# STRAIN.net
KiCad netlist of a schematic drawn in Altium Designer
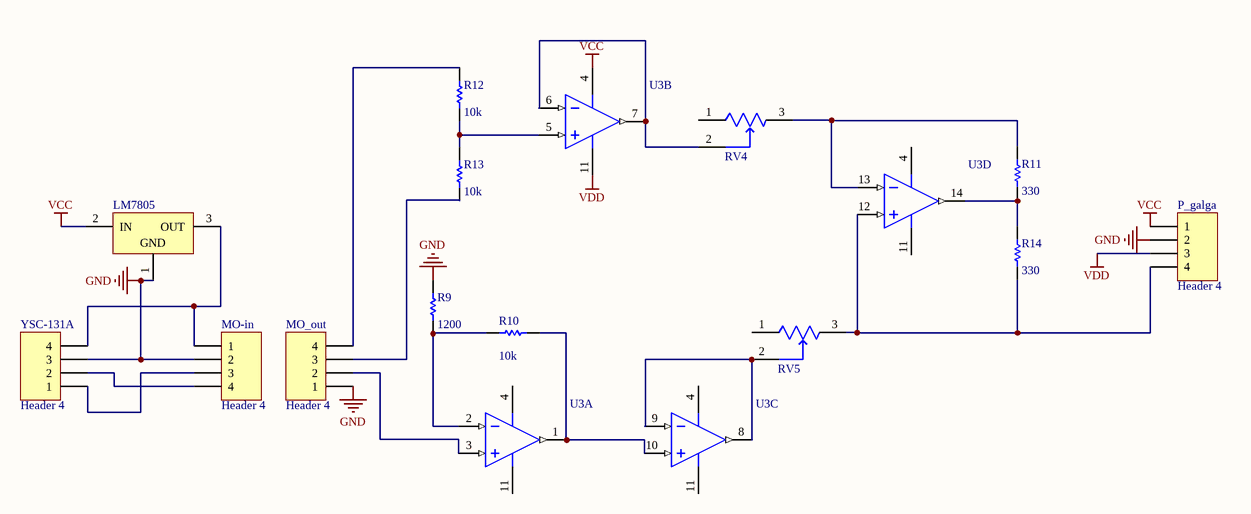
[diagram p0: STRAIN.SchDoc]

(export (version "E")
  (design (tool "Eeschema 10.0.6"))
  (components
    (comp (ref "LM7805")
      (value "LM7905CT/NOPB")
      (footprint "NDE0003A")
      (description "3-Terminal Negative Regulator, 3-pin TO-220, Pb-Free")
      (fields (field (name "MANUFACTURER") "Texas Instruments"))
      (libsource (lib "Altium Content Vault") (part "PM-REG-LM7905-SIL3"))
    )
    (comp (ref "MO-in")
      (value "Header 4")
      (footprint "HDR1X4")
      (description "Header, 4-Pin")
      (fields (field (name "PUBLISHER") "Altium Limited"))
      (libsource (lib "Miscellaneous Connectors") (part "Header 4"))
    )
    (comp (ref "MO_out")
      (value "Header 4")
      (footprint "HDR1X4")
      (description "Header, 4-Pin")
      (fields (field (name "PUBLISHER") "Altium Limited"))
      (libsource (lib "") (part "Header 4_1"))
    )
    (comp (ref "P_galga")
      (value "Header 4")
      (footprint "HDR1X4")
      (description "Header, 4-Pin")
      (fields (field (name "PUBLISHER") "Altium Limited"))
      (libsource (lib "Miscellaneous Connectors") (part "Header 4"))
    )
    (comp (ref "R9")
      (value "1200")
      (footprint "AXIAL-0.3")
      (description "Resistor")
      (fields (field (name "Comment") "Res1") (field (name "PUBLISHER") "Altium Limited"))
      (libsource (lib "Miscellaneous Devices") (part "Res1"))
    )
    (comp (ref "R10")
      (value "10k")
      (footprint "AXIAL-0.3")
      (description "Resistor")
      (fields (field (name "Comment") "Res1") (field (name "PUBLISHER") "Altium Limited"))
      (libsource (lib "Miscellaneous Devices") (part "Res1"))
    )
    (comp (ref "R11")
      (value "330")
      (footprint "AXIAL-0.3")
      (description "Resistor")
      (fields (field (name "Comment") "Res1") (field (name "PUBLISHER") "Altium Limited"))
      (libsource (lib "Miscellaneous Devices") (part "Res1"))
    )
    (comp (ref "R12")
      (value "10k")
      (footprint "AXIAL-0.3")
      (description "Resistor")
      (fields (field (name "Comment") "Res1") (field (name "PUBLISHER") "Altium Limited"))
      (libsource (lib "Miscellaneous Devices") (part "Res1"))
    )
    (comp (ref "R13")
      (value "10k")
      (footprint "AXIAL-0.3")
      (description "Resistor")
      (fields (field (name "Comment") "Res1") (field (name "PUBLISHER") "Altium Limited"))
      (libsource (lib "Miscellaneous Devices") (part "Res1"))
    )
    (comp (ref "R14")
      (value "330")
      (footprint "AXIAL-0.3")
      (description "Resistor")
      (fields (field (name "Comment") "Res1") (field (name "PUBLISHER") "Altium Limited"))
      (libsource (lib "Miscellaneous Devices") (part "Res1"))
    )
    (comp (ref "RV4")
      (value "3296W-1-504LF")
      (footprint "FP-3296W-MFG")
      (description "TRIMMER 500K OHM 0.5W PC PIN TOP")
      (fields
        (field (name "MANUFACTURER") "Bourns")
        (field (name "OCTOPART") "https://octopart.com/3296w-1-504lf-bourns-143884")
      )
      (libsource (lib "Altium Content Vault") (part "8d460c8a6f7ec10b1759d1b9c49aa93"))
    )
    (comp (ref "RV5")
      (value "3296W-1-504LF")
      (footprint "FP-3296W-MFG")
      (description "TRIMMER 500K OHM 0.5W PC PIN TOP")
      (fields
        (field (name "MANUFACTURER") "Bourns")
        (field (name "OCTOPART") "https://octopart.com/3296w-1-504lf-bourns-143884")
      )
      (libsource (lib "Altium Content Vault") (part "8d460c8a6f7ec10b1759d1b9c49aa93"))
    )
    (comp (ref "U3")
      (value "LF347N")
      (footprint "N0014A")
      (description "Wide Bandwidth Quad JFET Input Operational Amplifier, 14-pin MDIP")
      (fields (field (name "MANUFACTURER") "Texas Instruments"))
      (libsource (lib "Altium Content Vault") (part "AMP-OPA-LF147-14"))
    )
    (comp (ref "YSC-131A")
      (value "Header 4")
      (footprint "HDR1X4")
      (description "Header, 4-Pin")
      (fields (field (name "PUBLISHER") "Altium Limited"))
      (libsource (lib "") (part "Header 4_1"))
    )
  )
  (nets
    (net (code "1") (name "GND") (class "Default")
      (node (ref "LM7805") (pin "1") (pinfunction "GND_1") (pintype "power_in"))
      (node (ref "MO-in") (pin "2") (pinfunction "2_2") (pintype "passive"))
      (node (ref "MO_out") (pin "1") (pinfunction "1_1") (pintype "passive"))
      (node (ref "P_galga") (pin "2") (pinfunction "2_2") (pintype "passive"))
      (node (ref "R9") (pin "2") (pinfunction "2_2") (pintype "passive"))
      (node (ref "YSC-131A") (pin "3") (pinfunction "3_3") (pintype "passive"))
    )
    (net (code "2") (name "Net-(LM7805-OUT)") (class "Default")
      (node (ref "LM7805") (pin "3") (pinfunction "OUT_3") (pintype "power_in"))
      (node (ref "MO-in") (pin "1") (pinfunction "1_1") (pintype "passive"))
      (node (ref "YSC-131A") (pin "4") (pinfunction "4_4") (pintype "passive"))
    )
    (net (code "3") (name "Net-(MO-in-Pad3)") (class "Default")
      (node (ref "MO-in") (pin "3") (pinfunction "3_3") (pintype "passive"))
      (node (ref "YSC-131A") (pin "1") (pinfunction "1_1") (pintype "passive"))
    )
    (net (code "4") (name "Net-(MO-in-Pad4)") (class "Default")
      (node (ref "MO-in") (pin "4") (pinfunction "4_4") (pintype "passive"))
      (node (ref "YSC-131A") (pin "2") (pinfunction "2_2") (pintype "passive"))
    )
    (net (code "5") (name "Net-(MO_out-Pad3)") (class "Default")
      (node (ref "MO_out") (pin "3") (pinfunction "3_3") (pintype "passive"))
      (node (ref "R13") (pin "1") (pinfunction "1_1") (pintype "passive"))
    )
    (net (code "6") (name "Net-(MO_out-Pad4)") (class "Default")
      (node (ref "MO_out") (pin "4") (pinfunction "4_4") (pintype "passive"))
      (node (ref "R12") (pin "2") (pinfunction "2_2") (pintype "passive"))
    )
    (net (code "7") (name "Net-(RV4-CW)") (class "Default")
      (node (ref "R11") (pin "2") (pinfunction "2_2") (pintype "passive"))
      (node (ref "RV4") (pin "3") (pinfunction "CW_3") (pintype "passive"))
      (node (ref "U3") (pin "13") (pinfunction "IN4-_13") (pintype "input"))
    )
    (net (code "8") (name "Net-(RV4-WIPER)") (class "Default")
      (node (ref "RV4") (pin "2") (pinfunction "WIPER_2") (pintype "passive"))
      (node (ref "U3") (pin "6") (pinfunction "IN2-_6") (pintype "input"))
      (node (ref "U3") (pin "7") (pinfunction "OUT2_7") (pintype "output"))
    )
    (net (code "9") (name "Net-(RV5-CW)") (class "Default")
      (node (ref "P_galga") (pin "4") (pinfunction "4_4") (pintype "passive"))
      (node (ref "R14") (pin "1") (pinfunction "1_1") (pintype "passive"))
      (node (ref "RV5") (pin "3") (pinfunction "CW_3") (pintype "passive"))
      (node (ref "U3") (pin "12") (pinfunction "IN4+_12") (pintype "input"))
    )
    (net (code "10") (name "Net-(RV5-WIPER)") (class "Default")
      (node (ref "RV5") (pin "2") (pinfunction "WIPER_2") (pintype "passive"))
      (node (ref "U3") (pin "8") (pinfunction "OUT3_8") (pintype "output"))
      (node (ref "U3") (pin "9") (pinfunction "IN3-_9") (pintype "input"))
    )
    (net (code "11") (name "Net-(U3A-IN1+)") (class "Default")
      (node (ref "MO_out") (pin "2") (pinfunction "2_2") (pintype "passive"))
      (node (ref "U3") (pin "3") (pinfunction "IN1+_3") (pintype "input"))
    )
    (net (code "12") (name "Net-(U3A-IN1-)") (class "Default")
      (node (ref "R10") (pin "1") (pinfunction "1_1") (pintype "passive"))
      (node (ref "R9") (pin "1") (pinfunction "1_1") (pintype "passive"))
      (node (ref "U3") (pin "2") (pinfunction "IN1-_2") (pintype "input"))
    )
    (net (code "13") (name "Net-(U3A-OUT1)") (class "Default")
      (node (ref "R10") (pin "2") (pinfunction "2_2") (pintype "passive"))
      (node (ref "U3") (pin "1") (pinfunction "OUT1_1") (pintype "output"))
      (node (ref "U3") (pin "10") (pinfunction "IN3+_10") (pintype "input"))
    )
    (net (code "14") (name "Net-(U3B-IN2+)") (class "Default")
      (node (ref "R12") (pin "1") (pinfunction "1_1") (pintype "passive"))
      (node (ref "R13") (pin "2") (pinfunction "2_2") (pintype "passive"))
      (node (ref "U3") (pin "5") (pinfunction "IN2+_5") (pintype "input"))
    )
    (net (code "15") (name "Net-(U3D-OUT4)") (class "Default")
      (node (ref "R11") (pin "1") (pinfunction "1_1") (pintype "passive"))
      (node (ref "R14") (pin "2") (pinfunction "2_2") (pintype "passive"))
      (node (ref "U3") (pin "14") (pinfunction "OUT4_14") (pintype "output"))
    )
    (net (code "16") (name "VCC") (class "Default")
      (node (ref "LM7805") (pin "2") (pinfunction "IN_2") (pintype "power_in"))
      (node (ref "P_galga") (pin "1") (pinfunction "1_1") (pintype "passive"))
      (node (ref "U3") (pin "4") (pinfunction "V+_4") (pintype "power_in"))
    )
    (net (code "17") (name "VDD") (class "Default")
      (node (ref "P_galga") (pin "3") (pinfunction "3_3") (pintype "passive"))
      (node (ref "U3") (pin "11") (pinfunction "V-_11") (pintype "power_in"))
    )
    (net (code "18") (name "unconnected-(RV4-CCW-Pad1)") (class "Default")
      (node (ref "RV4") (pin "1") (pinfunction "CCW_1") (pintype "passive"))
    )
    (net (code "19") (name "unconnected-(RV5-CCW-Pad1)") (class "Default")
      (node (ref "RV5") (pin "1") (pinfunction "CCW_1") (pintype "passive"))
    )
    (net (code "20") (name "unconnected-(U3A-V+-Pad4)") (class "Default")
      (node (ref "U3") (pin "4") (pinfunction "V+_4") (pintype "power_in"))
    )
    (net (code "21") (name "unconnected-(U3A-V--Pad11)") (class "Default")
      (node (ref "U3") (pin "11") (pinfunction "V-_11") (pintype "power_in"))
    )
    (net (code "22") (name "unconnected-(U3C-V+-Pad4)") (class "Default")
      (node (ref "U3") (pin "4") (pinfunction "V+_4") (pintype "power_in"))
    )
    (net (code "23") (name "unconnected-(U3C-V--Pad11)") (class "Default")
      (node (ref "U3") (pin "11") (pinfunction "V-_11") (pintype "power_in"))
    )
    (net (code "24") (name "unconnected-(U3D-V+-Pad4)") (class "Default")
      (node (ref "U3") (pin "4") (pinfunction "V+_4") (pintype "power_in"))
    )
    (net (code "25") (name "unconnected-(U3D-V--Pad11)") (class "Default")
      (node (ref "U3") (pin "11") (pinfunction "V-_11") (pintype "power_in"))
    )
  )
)
